# 05_-_POWER_SUPPY.net
KiCad netlist of a schematic drawn in Altium Designer
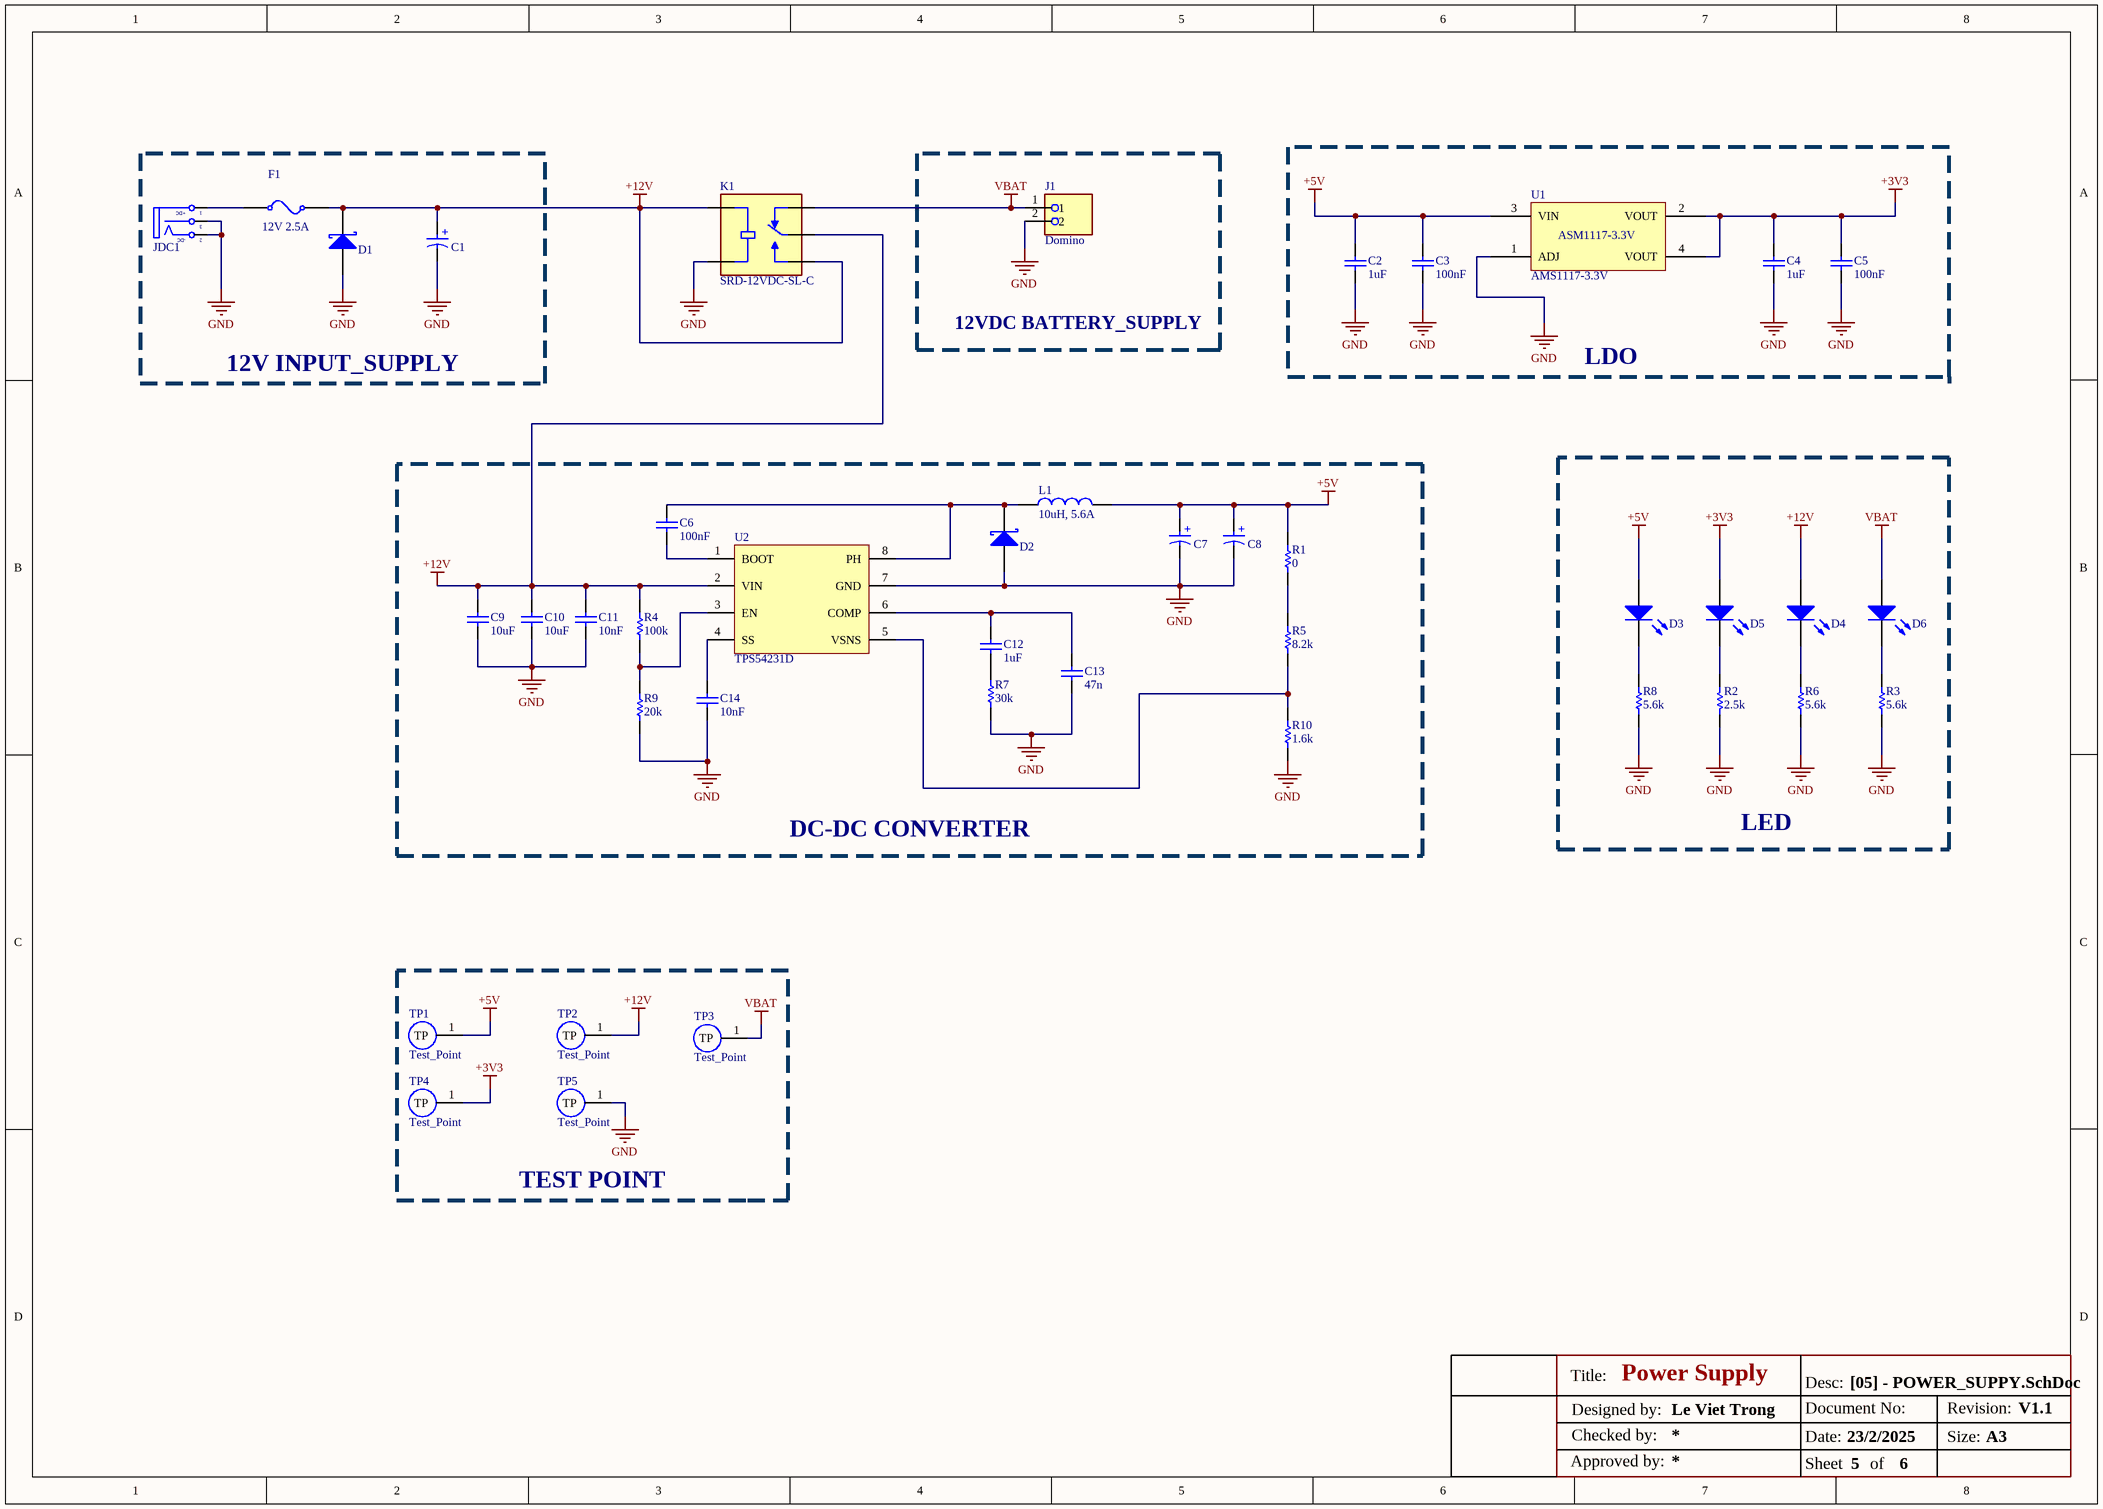
[diagram p0: [05] - POWER_SUPPY.SchDoc]

(export (version "E")
  (design (tool "Eeschema 10.0.6"))
  (components
    (comp (ref "C1")
      (value "22uF")
      (footprint "WCAP-ASLI_D4H5.5")
      (description "V-Chip, D4 x H5.5mm, 22uF, 16V")
      (libsource (lib "SMIOT_Lib_Schematic") (part "865080340003"))
    )
    (comp (ref "C2")
      (value "1uF")
      (footprint "CAP_0603")
      (description "CAP, size 0603, 1uF")
      (libsource (lib "SMIOT_Lib_Schematic") (part "01060310510"))
    )
    (comp (ref "C3")
      (value "100nF")
      (footprint "CAP_0603")
      (description "CAP, size 0603, 100nF")
      (libsource (lib "SMIOT_Lib_Schematic") (part "01060310410"))
    )
    (comp (ref "C4")
      (value "1uF")
      (footprint "CAP_0603")
      (description "CAP, size 0603, 1uF")
      (libsource (lib "SMIOT_Lib_Schematic") (part "01060310510"))
    )
    (comp (ref "C5")
      (value "100nF")
      (footprint "CAP_0603")
      (description "CAP, size 0603, 100nF")
      (libsource (lib "SMIOT_Lib_Schematic") (part "01060310410"))
    )
    (comp (ref "C6")
      (value "100nF")
      (footprint "CAP_0603")
      (description "CAP, size 0603, 100nF")
      (libsource (lib "SMIOT_Lib_Schematic") (part "01060310410"))
    )
    (comp (ref "C7")
      (value "47uF")
      (footprint "WCAP-ASLI_D5H5.5")
      (description "V-Chip, D5 x H5.5mm, 47uF, 16V")
      (libsource (lib "SMIOT_Lib_Schematic") (part "Tụ nhôm SMD"))
    )
    (comp (ref "C8")
      (value "47uF")
      (footprint "WCAP-ASLI_D5H5.5")
      (description "V-Chip, D5 x H5.5mm, 47uF, 16V")
      (libsource (lib "SMIOT_Lib_Schematic") (part "Tụ nhôm SMD"))
    )
    (comp (ref "C9")
      (value "10uF")
      (footprint "CAP_0603")
      (description "CAP, size 0603,10uF")
      (libsource (lib "SMIOT_Lib_Schematic") (part "01060310010"))
    )
    (comp (ref "C10")
      (value "10uF")
      (footprint "CAP_0603")
      (description "CAP, size 0603,10uF")
      (libsource (lib "SMIOT_Lib_Schematic") (part "01060310010"))
    )
    (comp (ref "C11")
      (value "10nF")
      (footprint "CAP_0603")
      (description "CAP, size 0603, 10nF")
      (libsource (lib "SMIOT_Lib_Schematic") (part "01060310310"))
    )
    (comp (ref "C12")
      (value "1uF")
      (footprint "CAP_0603")
      (description "CAP, size 0603, 1uF")
      (libsource (lib "SMIOT_Lib_Schematic") (part "01060310510"))
    )
    (comp (ref "C13")
      (value "47n")
      (footprint "CAP_0603")
      (description "CAP, size 0603, 47nF")
      (libsource (lib "SMIOT_Lib_Schematic") (part "01060347310"))
    )
    (comp (ref "C14")
      (value "10nF")
      (footprint "CAP_0603")
      (description "CAP, size 0603, 10nF")
      (libsource (lib "SMIOT_Lib_Schematic") (part "01060310310"))
    )
    (comp (ref "D1")
      (value "D Schottky")
      (footprint "SS34")
      (description "Schottky Diode")
      (fields (field (name "PUBLISHER") "Altium Limited"))
      (libsource (lib "Board_C24") (part "D Schottky"))
    )
    (comp (ref "D2")
      (value "D Schottky")
      (footprint "SS34")
      (description "Schottky Diode")
      (fields (field (name "PUBLISHER") "Altium Limited"))
      (libsource (lib "SMIOT_Lib_Schematic") (part "D Schottky"))
    )
    (comp (ref "D3")
      (value "LED SMD")
      (footprint "LED_0805_Blue")
      (description "LED")
      (libsource (lib "SMIOT_Lib_Schematic") (part "LED SMD"))
    )
    (comp (ref "D4")
      (value "LED SMD")
      (footprint "LED_0805_Blue")
      (description "LED")
      (libsource (lib "SMIOT_Lib_Schematic") (part "LED SMD"))
    )
    (comp (ref "D5")
      (value "LED SMD")
      (footprint "LED_0805_Blue")
      (description "LED")
      (libsource (lib "SMIOT_Lib_Schematic") (part "LED SMD"))
    )
    (comp (ref "D6")
      (value "LED SMD")
      (footprint "LED_0805_Blue")
      (description "LED")
      (libsource (lib "SMIOT_Lib_Schematic") (part "LED SMD"))
    )
    (comp (ref "F1")
      (value "12V 2.5A")
      (footprint "Fuse_SMD_1812")
      (description "Resettable Fuse, Size 1812, 8V, 2A")
      (fields (field (name "MANUFACTURER") "Littelfuse"))
      (libsource (lib "SMIOT_Lib_Schematic") (part "061812200008"))
    )
    (comp (ref "J1")
      (value "Domino")
      (footprint "PHOENIX_1935161")
      (description "PCB Terminal Screw 5mm 16AWG 400V 17.5A 2 Position COMBICON PT Series ¦ Phoenix Contact 1935161")
      (fields (field (name "MF") "Phoenix Contact") (field (name "MP") "1935161"))
      (libsource (lib "Domino") (part "Domino"))
    )
    (comp (ref "JDC1")
      (value "Jack DC")
      (footprint "DC-IN")
      (description "Jack DC input")
      (libsource (lib "SMIOT_Lib_Schematic") (part "Jack DC"))
    )
    (comp (ref "K1")
      (value "SRD-12VDC-SL-C")
      (footprint "RELAY_SRD-12VDC-SL-C")
      (description "General Purpose Non Latching 12VDC SPDT Through Hole Relays RoHS")
      (fields (field (name "MF") "Songle Relay"))
      (libsource (lib "RELAY") (part "SRD-12VDC-SL-C"))
    )
    (comp (ref "L1")
      (value "10uH, 5.6A")
      (footprint "WE-PD2A_5848")
      (description "WE-PD2A SMT Power Inductor, size 5848, 10uH, 2.2A")
      (fields
        (field (name "MANUFACTURER PART NUMBER") "78477410")
        (field (name "MANUFACTURER") "Wurth Elektronik")
      )
      (libsource (lib "SMIOT_Lib_Schematic") (part "78477410"))
    )
    (comp (ref "R1")
      (value "0")
      (footprint "resistor_0603")
      (description "RES, 0 Ohm, size 0603, 1%")
      (libsource (lib "SMIOT_Lib_Schematic") (part "0006030001"))
    )
    (comp (ref "R2")
      (value "2.5k")
      (footprint "resistor_0603")
      (description "RES, 2.5K Ohm, size 0603, 5%")
      (libsource (lib "SMIOT_Lib_Schematic") (part "0006032525"))
    )
    (comp (ref "R3")
      (value "5.6k")
      (footprint "resistor_0603")
      (description "RES, 5.6k Ohm, size 0603, 1%")
      (libsource (lib "SMIOT_Lib_Schematic") (part "0006035621"))
    )
    (comp (ref "R4")
      (value "100k")
      (footprint "resistor_0603")
      (description "RES, 100k Ohm, size 0603, 1%")
      (libsource (lib "SMIOT_Lib_Schematic") (part "0006031041"))
    )
    (comp (ref "R5")
      (value "8.2k")
      (footprint "resistor_0603")
      (description "RES, 8.2 kOhms, size 0603, 1%")
      (libsource (lib "SMIOT_Lib_Schematic") (part "0006038251"))
    )
    (comp (ref "R6")
      (value "5.6k")
      (footprint "resistor_0603")
      (description "RES, 5.6k Ohm, size 0603, 1%")
      (libsource (lib "SMIOT_Lib_Schematic") (part "0006035621"))
    )
    (comp (ref "R7")
      (value "30k")
      (footprint "resistor_0603")
      (description "RES, 30k Ohm, size 0603, 1%")
      (libsource (lib "SMIOT_Lib_Schematic") (part "0006033205"))
    )
    (comp (ref "R8")
      (value "5.6k")
      (footprint "resistor_0603")
      (description "RES, 5.6k Ohm, size 0603, 1%")
      (libsource (lib "SMIOT_Lib_Schematic") (part "0006035621"))
    )
    (comp (ref "R9")
      (value "20k")
      (footprint "resistor_0603")
      (description "RES, 20 kOhms, size 0603, 1%")
      (libsource (lib "SMIOT_Lib_Schematic") (part "0006032031"))
    )
    (comp (ref "R10")
      (value "1.6k")
      (footprint "resistor_0603")
      (description "RES, 1.5 kOhms, size 0603, 1%")
      (libsource (lib "SMIOT_Lib_Schematic") (part "0006031521"))
    )
    (comp (ref "TP1")
      (value "Test_Point")
      (footprint "TP_2MM")
      (description "Test point, 2mm radius")
      (libsource (lib "SMIOT_Lib_Schematic") (part "Test_Point"))
    )
    (comp (ref "TP2")
      (value "Test_Point")
      (footprint "TP_2MM")
      (description "Test point, 2mm radius")
      (libsource (lib "SMIOT_Lib_Schematic") (part "Test_Point"))
    )
    (comp (ref "TP3")
      (value "Test_Point")
      (footprint "TP_2MM")
      (description "Test point, 2mm radius")
      (libsource (lib "SMIOT_Lib_Schematic") (part "Test_Point"))
    )
    (comp (ref "TP4")
      (value "Test_Point")
      (footprint "TP_2MM")
      (description "Test point, 2mm radius")
      (libsource (lib "SMIOT_Lib_Schematic") (part "Test_Point"))
    )
    (comp (ref "TP5")
      (value "Test_Point")
      (footprint "TP_2MM")
      (description "Test point, 2mm radius")
      (libsource (lib "SMIOT_Lib_Schematic") (part "Test_Point"))
    )
    (comp (ref "U1")
      (value "AMS1117-3.3V")
      (footprint "AMS1117-3.3V SOT223")
      (description "AMS1117-3.3V, OUT 3.3V 1A.")
      (fields (field (name "MANUFACTURER") "AMS"))
      (libsource (lib "SMIOT_Lib_Schematic") (part "AMS1117-3.3V"))
    )
    (comp (ref "U2")
      (value "TPS54231D")
      (footprint "SOIC8")
      (description "Buck Switching Regulator IC Positive Adjustable 0.8V 1 Output 2A 8-SOIC (0.154\", 3.90mm Width)")
      (fields (field (name "MFR") "Texas Instruments"))
      (libsource (lib "SMIOT_Lib_Schematic") (part "TPS54231"))
    )
  )
  (nets
    (net (code "1") (name "+3V3") (class "Default")
      (node (ref "C4") (pin "2") (pinfunction "2_2") (pintype "passive"))
      (node (ref "C5") (pin "2") (pinfunction "2_2") (pintype "passive"))
      (node (ref "D5") (pin "1") (pinfunction "A_1") (pintype "passive"))
      (node (ref "TP4") (pin "1") (pinfunction "TP_1") (pintype "passive"))
      (node (ref "U1") (pin "2") (pinfunction "VOUT_2") (pintype "passive"))
      (node (ref "U1") (pin "4") (pinfunction "VOUT_4") (pintype "power_in"))
    )
    (net (code "2") (name "+5V") (class "Default")
      (node (ref "C2") (pin "2") (pinfunction "2_2") (pintype "passive"))
      (node (ref "C3") (pin "2") (pinfunction "2_2") (pintype "passive"))
      (node (ref "C7") (pin "1") (pinfunction "P_1") (pintype "passive"))
      (node (ref "C8") (pin "1") (pinfunction "P_1") (pintype "passive"))
      (node (ref "D3") (pin "1") (pinfunction "A_1") (pintype "passive"))
      (node (ref "L1") (pin "2") (pinfunction "2_2") (pintype "passive"))
      (node (ref "R1") (pin "2") (pinfunction "2_2") (pintype "passive"))
      (node (ref "TP1") (pin "1") (pinfunction "TP_1") (pintype "passive"))
      (node (ref "U1") (pin "3") (pinfunction "VIN_3") (pintype "passive"))
    )
    (net (code "3") (name "+12V") (class "Default")
      (node (ref "C1") (pin "1") (pinfunction "P_1") (pintype "passive"))
      (node (ref "C10") (pin "2") (pinfunction "2_2") (pintype "passive"))
      (node (ref "C11") (pin "2") (pinfunction "2_2") (pintype "passive"))
      (node (ref "C9") (pin "2") (pinfunction "2_2") (pintype "passive"))
      (node (ref "D1") (pin "2") (pinfunction "K_2") (pintype "passive"))
      (node (ref "D4") (pin "1") (pinfunction "A_1") (pintype "passive"))
      (node (ref "F1") (pin "1") (pinfunction "1_1") (pintype "passive"))
      (node (ref "K1") (pin "COIL1") (pinfunction "COIL1_COIL1") (pintype "passive"))
      (node (ref "K1") (pin "COM") (pinfunction "COM_COM") (pintype "passive"))
      (node (ref "K1") (pin "NO") (pinfunction "NO_NO") (pintype "passive"))
      (node (ref "R4") (pin "2") (pinfunction "2_2") (pintype "passive"))
      (node (ref "TP2") (pin "1") (pinfunction "TP_1") (pintype "passive"))
      (node (ref "U2") (pin "2") (pinfunction "VIN_2") (pintype "passive"))
    )
    (net (code "4") (name "GND") (class "Default")
      (node (ref "C1") (pin "2") (pinfunction "N_2") (pintype "passive"))
      (node (ref "C10") (pin "1") (pinfunction "1_1") (pintype "passive"))
      (node (ref "C11") (pin "1") (pinfunction "1_1") (pintype "passive"))
      (node (ref "C13") (pin "1") (pinfunction "1_1") (pintype "passive"))
      (node (ref "C14") (pin "1") (pinfunction "1_1") (pintype "passive"))
      (node (ref "C2") (pin "1") (pinfunction "1_1") (pintype "passive"))
      (node (ref "C3") (pin "1") (pinfunction "1_1") (pintype "passive"))
      (node (ref "C4") (pin "1") (pinfunction "1_1") (pintype "passive"))
      (node (ref "C5") (pin "1") (pinfunction "1_1") (pintype "passive"))
      (node (ref "C7") (pin "2") (pinfunction "N_2") (pintype "passive"))
      (node (ref "C8") (pin "2") (pinfunction "N_2") (pintype "passive"))
      (node (ref "C9") (pin "1") (pinfunction "1_1") (pintype "passive"))
      (node (ref "D1") (pin "1") (pinfunction "A_1") (pintype "passive"))
      (node (ref "D2") (pin "1") (pinfunction "A_1") (pintype "passive"))
      (node (ref "J1") (pin "2") (pinfunction "2_2") (pintype "passive"))
      (node (ref "JDC1") (pin "2") (pinfunction "TN_2") (pintype "passive"))
      (node (ref "JDC1") (pin "3") (pinfunction "S_3") (pintype "power_in"))
      (node (ref "K1") (pin "COIL2") (pinfunction "COIL2_COIL2") (pintype "passive"))
      (node (ref "R10") (pin "1") (pinfunction "1_1") (pintype "passive"))
      (node (ref "R2") (pin "1") (pinfunction "1_1") (pintype "passive"))
      (node (ref "R3") (pin "1") (pinfunction "1_1") (pintype "passive"))
      (node (ref "R6") (pin "1") (pinfunction "1_1") (pintype "passive"))
      (node (ref "R7") (pin "1") (pinfunction "1_1") (pintype "passive"))
      (node (ref "R8") (pin "1") (pinfunction "1_1") (pintype "passive"))
      (node (ref "R9") (pin "1") (pinfunction "1_1") (pintype "passive"))
      (node (ref "TP5") (pin "1") (pinfunction "TP_1") (pintype "passive"))
      (node (ref "U1") (pin "1") (pinfunction "ADJ_1") (pintype "power_in"))
      (node (ref "U2") (pin "7") (pinfunction "GND_7") (pintype "passive"))
    )
    (net (code "5") (name "Net-(C12-Pad2)") (class "Default")
      (node (ref "C12") (pin "2") (pinfunction "2_2") (pintype "passive"))
      (node (ref "R7") (pin "2") (pinfunction "2_2") (pintype "passive"))
    )
    (net (code "6") (name "Net-(D2-K)") (class "Default")
      (node (ref "C6") (pin "2") (pinfunction "2_2") (pintype "passive"))
      (node (ref "D2") (pin "2") (pinfunction "K_2") (pintype "passive"))
      (node (ref "L1") (pin "1") (pinfunction "1_1") (pintype "passive"))
      (node (ref "U2") (pin "8") (pinfunction "PH_8") (pintype "passive"))
    )
    (net (code "7") (name "Net-(D3-K)") (class "Default")
      (node (ref "D3") (pin "2") (pinfunction "K_2") (pintype "passive"))
      (node (ref "R8") (pin "2") (pinfunction "2_2") (pintype "passive"))
    )
    (net (code "8") (name "Net-(D4-K)") (class "Default")
      (node (ref "D4") (pin "2") (pinfunction "K_2") (pintype "passive"))
      (node (ref "R6") (pin "2") (pinfunction "2_2") (pintype "passive"))
    )
    (net (code "9") (name "Net-(D5-K)") (class "Default")
      (node (ref "D5") (pin "2") (pinfunction "K_2") (pintype "passive"))
      (node (ref "R2") (pin "2") (pinfunction "2_2") (pintype "passive"))
    )
    (net (code "10") (name "Net-(D6-K)") (class "Default")
      (node (ref "D6") (pin "2") (pinfunction "K_2") (pintype "passive"))
      (node (ref "R3") (pin "2") (pinfunction "2_2") (pintype "passive"))
    )
    (net (code "11") (name "Net-(JDC1-T)") (class "Default")
      (node (ref "F1") (pin "0") (pinfunction "0_0") (pintype "passive"))
      (node (ref "JDC1") (pin "1") (pinfunction "T_1") (pintype "passive"))
    )
    (net (code "12") (name "Net-(R1-Pad1)") (class "Default")
      (node (ref "R1") (pin "1") (pinfunction "1_1") (pintype "passive"))
      (node (ref "R5") (pin "2") (pinfunction "2_2") (pintype "passive"))
    )
    (net (code "13") (name "Net-(U2-BOOT)") (class "Default")
      (node (ref "C6") (pin "1") (pinfunction "1_1") (pintype "passive"))
      (node (ref "U2") (pin "1") (pinfunction "BOOT_1") (pintype "passive"))
    )
    (net (code "14") (name "Net-(U2-COMP)") (class "Default")
      (node (ref "C12") (pin "1") (pinfunction "1_1") (pintype "passive"))
      (node (ref "C13") (pin "2") (pinfunction "2_2") (pintype "passive"))
      (node (ref "U2") (pin "6") (pinfunction "COMP_6") (pintype "passive"))
    )
    (net (code "15") (name "Net-(U2-EN)") (class "Default")
      (node (ref "R4") (pin "1") (pinfunction "1_1") (pintype "passive"))
      (node (ref "R9") (pin "2") (pinfunction "2_2") (pintype "passive"))
      (node (ref "U2") (pin "3") (pinfunction "EN_3") (pintype "passive"))
    )
    (net (code "16") (name "Net-(U2-SS)") (class "Default")
      (node (ref "C14") (pin "2") (pinfunction "2_2") (pintype "passive"))
      (node (ref "U2") (pin "4") (pinfunction "SS_4") (pintype "passive"))
    )
    (net (code "17") (name "Net-(U2-VSNS)") (class "Default")
      (node (ref "R10") (pin "2") (pinfunction "2_2") (pintype "passive"))
      (node (ref "R5") (pin "1") (pinfunction "1_1") (pintype "passive"))
      (node (ref "U2") (pin "5") (pinfunction "VSNS_5") (pintype "passive"))
    )
    (net (code "18") (name "VBAT") (class "Default")
      (node (ref "D6") (pin "1") (pinfunction "A_1") (pintype "passive"))
      (node (ref "J1") (pin "1") (pinfunction "1_1") (pintype "passive"))
      (node (ref "K1") (pin "NC") (pinfunction "NC_NC") (pintype "passive"))
      (node (ref "TP3") (pin "1") (pinfunction "TP_1") (pintype "passive"))
    )
  )
)
